# onetesla.net
KiCad netlist of a schematic drawn in EAGLE
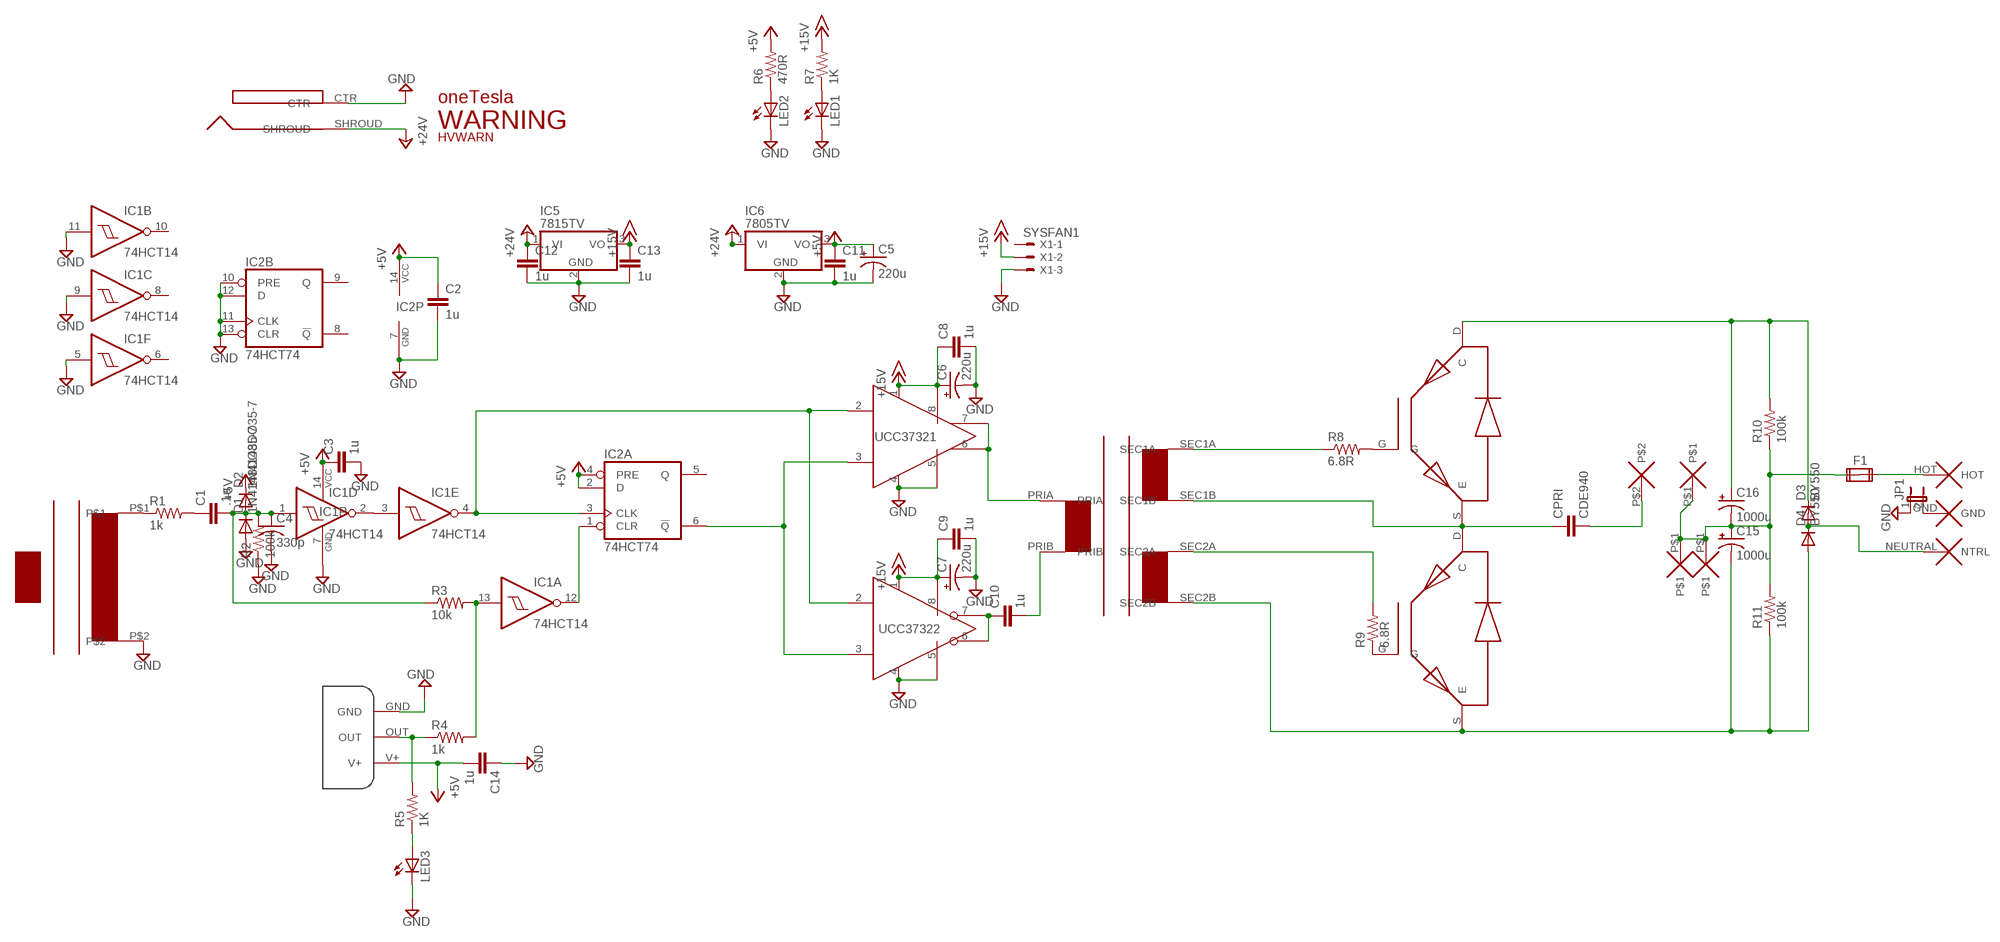
[diagram p0: schematic, sheet 1]

(export (version "E")
  (design (tool "Eeschema 10.0.6"))
  (components
    (comp (ref "C1")
      (value ".1u")
      (footprint "eagle-import:C050-024X044")
      (libsource (lib "eagle-import") (part "C-EU050-024X044"))
    )
    (comp (ref "C2")
      (value "1u")
      (footprint "eagle-import:C050-024X044")
      (libsource (lib "eagle-import") (part "C-EU050-024X044"))
    )
    (comp (ref "C3")
      (value "1u")
      (footprint "eagle-import:C050-024X044")
      (libsource (lib "eagle-import") (part "C-EU050-024X044"))
    )
    (comp (ref "C4")
      (value "330p")
      (footprint "eagle-import:C025-024X044")
      (libsource (lib "eagle-import") (part "C-US025-024X044"))
    )
    (comp (ref "C5")
      (value "220u")
      (footprint "eagle-import:E5-10,5")
      (libsource (lib "eagle-import") (part "CPOL-USE5-10.5"))
    )
    (comp (ref "C6")
      (value "220u")
      (footprint "eagle-import:E5-10,5")
      (libsource (lib "eagle-import") (part "CPOL-USE5-10.5"))
    )
    (comp (ref "C7")
      (value "220u")
      (footprint "eagle-import:E5-10,5")
      (libsource (lib "eagle-import") (part "CPOL-USE5-10.5"))
    )
    (comp (ref "C8")
      (value "1u")
      (footprint "eagle-import:C050-024X044")
      (libsource (lib "eagle-import") (part "C-EU050-024X044"))
    )
    (comp (ref "C9")
      (value "1u")
      (footprint "eagle-import:C050-024X044")
      (libsource (lib "eagle-import") (part "C-EU050-024X044"))
    )
    (comp (ref "C10")
      (value "1u")
      (footprint "eagle-import:C050-024X044")
      (libsource (lib "eagle-import") (part "C-EU050-024X044"))
    )
    (comp (ref "C11")
      (value "1u")
      (footprint "eagle-import:C050-024X044")
      (libsource (lib "eagle-import") (part "C-EU050-024X044"))
    )
    (comp (ref "C12")
      (value "1u")
      (footprint "eagle-import:C050-024X044")
      (libsource (lib "eagle-import") (part "C-EU050-024X044"))
    )
    (comp (ref "C13")
      (value "1u")
      (footprint "eagle-import:C050-024X044")
      (libsource (lib "eagle-import") (part "C-EU050-024X044"))
    )
    (comp (ref "C14")
      (value "1u")
      (footprint "eagle-import:C050-024X044")
      (libsource (lib "eagle-import") (part "C-EU050-024X044"))
    )
    (comp (ref "C15")
      (value "1000u")
      (footprint "eagle-import:EB25D")
      (libsource (lib "eagle-import") (part "CPOL-USE10-25"))
    )
    (comp (ref "C16")
      (value "1000u")
      (footprint "eagle-import:EB25D")
      (libsource (lib "eagle-import") (part "CPOL-USE10-25"))
    )
    (comp (ref "CPRI")
      (value "CDE940")
      (footprint "eagle-import:CDE940")
      (libsource (lib "eagle-import") (part "CDE940"))
    )
    (comp (ref "CT1")
      (value "TRIAD_CT")
      (footprint "eagle-import:CT2")
      (libsource (lib "eagle-import") (part "TRIAD_CT"))
    )
    (comp (ref "D1")
      (value "1N4148DO35-7")
      (footprint "eagle-import:DO35-7")
      (libsource (lib "eagle-import") (part "1N4148DO35-7"))
    )
    (comp (ref "D2")
      (value "1N4148DO35-7")
      (footprint "eagle-import:DO35-7")
      (libsource (lib "eagle-import") (part "1N4148DO35-7"))
    )
    (comp (ref "D3")
      (value "BY550")
      (footprint "eagle-import:DO27-15")
      (libsource (lib "eagle-import") (part "BY550"))
    )
    (comp (ref "D4")
      (value "BY550")
      (footprint "eagle-import:DO27-15")
      (libsource (lib "eagle-import") (part "BY550"))
    )
    (comp (ref "F1")
      (value "FUSE2P")
      (footprint "eagle-import:FUSE1")
      (libsource (lib "eagle-import") (part "FUSE2P"))
    )
    (comp (ref "FB1")
      (value "IFD95_OPTO")
      (footprint "eagle-import:IFD95")
      (libsource (lib "eagle-import") (part "IFD95_OPTO"))
    )
    (comp (ref "IC1")
      (value "74HCT14")
      (footprint "eagle-import:DIL14")
      (libsource (lib "eagle-import") (part "7414NLS"))
    )
    (comp (ref "IC2")
      (value "74HCT74")
      (footprint "eagle-import:DIL14")
      (libsource (lib "eagle-import") (part "7474NLS"))
    )
    (comp (ref "IC3")
      (value "UCC37321DIL8")
      (footprint "eagle-import:DIL08")
      (libsource (lib "eagle-import") (part "UCC37321DIL8"))
    )
    (comp (ref "IC4")
      (value "UCC37322DIL8")
      (footprint "eagle-import:DIL08")
      (libsource (lib "eagle-import") (part "UCC37322DIL8"))
    )
    (comp (ref "IC5")
      (value "7815TV")
      (footprint "eagle-import:TO220V")
      (libsource (lib "eagle-import") (part "78TV15"))
    )
    (comp (ref "IC6")
      (value "7805TV")
      (footprint "eagle-import:TO220V")
      (libsource (lib "eagle-import") (part "78TV05"))
    )
    (comp (ref "J1")
      (value "DC-IN")
      (footprint "eagle-import:DJC0202")
      (libsource (lib "eagle-import") (part "PJ-037B"))
    )
    (comp (ref "J2")
      (value "IEC")
      (footprint "eagle-import:IECPORT")
      (libsource (lib "eagle-import") (part "IEC"))
    )
    (comp (ref "JP1")
      (value "JP1E")
      (footprint "eagle-import:JP1")
      (libsource (lib "eagle-import") (part "JP1E"))
    )
    (comp (ref "LED1")
      (value "LED5MM")
      (footprint "eagle-import:LED5MM")
      (libsource (lib "eagle-import") (part "LED5MM"))
    )
    (comp (ref "LED2")
      (value "LED5MM")
      (footprint "eagle-import:LED5MM")
      (libsource (lib "eagle-import") (part "LED5MM"))
    )
    (comp (ref "LED3")
      (value "LED5MM")
      (footprint "eagle-import:LED5MM")
      (libsource (lib "eagle-import") (part "LED5MM"))
    )
    (comp (ref "LPRI")
      (value "2TERMINAL")
      (footprint "eagle-import:2TERMINAL")
      (libsource (lib "eagle-import") (part "2TERMINAL"))
    )
    (comp (ref "Q1")
      (value "FGA60N65SMD")
      (footprint "eagle-import:TO247BV")
      (libsource (lib "eagle-import") (part "FGH40N60SMD"))
    )
    (comp (ref "Q2")
      (value "FGA60N65SMD")
      (footprint "eagle-import:TO247BV")
      (libsource (lib "eagle-import") (part "FGH40N60SMD"))
    )
    (comp (ref "R1")
      (value "1k")
      (footprint "eagle-import:0922_22")
      (libsource (lib "eagle-import") (part "RES_5W"))
    )
    (comp (ref "R2")
      (value "100k")
      (footprint "eagle-import:0204_7")
      (libsource (lib "eagle-import") (part "resistor_R-US_0204/7"))
    )
    (comp (ref "R3")
      (value "10k")
      (footprint "eagle-import:0204_7")
      (libsource (lib "eagle-import") (part "resistor_R-US_0204/7"))
    )
    (comp (ref "R4")
      (value "1k")
      (footprint "eagle-import:0204_7")
      (libsource (lib "eagle-import") (part "resistor_R-US_0204/7"))
    )
    (comp (ref "R5")
      (value "1K")
      (footprint "eagle-import:0207_7")
      (libsource (lib "eagle-import") (part "R-US_0207/7"))
    )
    (comp (ref "R6")
      (value "470R")
      (footprint "eagle-import:0207_7")
      (libsource (lib "eagle-import") (part "R-US_0207/7"))
    )
    (comp (ref "R7")
      (value "1K")
      (footprint "eagle-import:0207_7")
      (libsource (lib "eagle-import") (part "R-US_0207/7"))
    )
    (comp (ref "R8")
      (value "6.8R")
      (footprint "eagle-import:0309V")
      (libsource (lib "eagle-import") (part "R-US_0309/V"))
    )
    (comp (ref "R9")
      (value "6.8R")
      (footprint "eagle-import:0309V")
      (libsource (lib "eagle-import") (part "R-US_0309/V"))
    )
    (comp (ref "R10")
      (value "100k")
      (footprint "eagle-import:0309_10")
      (libsource (lib "eagle-import") (part "resistor_R-US_0309/10"))
    )
    (comp (ref "R11")
      (value "100k")
      (footprint "eagle-import:0309_10")
      (libsource (lib "eagle-import") (part "resistor_R-US_0309/10"))
    )
    (comp (ref "U$1")
      (value "LOGO")
      (footprint "eagle-import:LOGO")
      (libsource (lib "eagle-import") (part "LOGO"))
    )
    (comp (ref "U$2")
      (value "GDT")
      (footprint "eagle-import:GDT")
      (libsource (lib "eagle-import") (part "GDT"))
    )
    (comp (ref "U$3")
      (value "WARNING")
      (footprint "eagle-import:WARNING")
      (libsource (lib "eagle-import") (part "WARNING"))
    )
    (comp (ref "U$4")
      (value "HVWARNING")
      (footprint "eagle-import:HVWARNING")
      (libsource (lib "eagle-import") (part "HVWARNING"))
    )
    (comp (ref "U$9")
      (value "12AWG_PAD")
      (footprint "eagle-import:12AWG_PAD")
      (libsource (lib "eagle-import") (part "12AWG_PAD"))
    )
    (comp (ref "U$11")
      (value "12AWG_PAD")
      (footprint "eagle-import:12AWG_PAD")
      (libsource (lib "eagle-import") (part "12AWG_PAD"))
    )
    (comp (ref "X1")
      (value "SYSFAN1")
      (footprint "eagle-import:22-23-2031")
      (fields (field (name "MF") "MOLEX") (field (name "MPN") "22-23-2031"))
      (libsource (lib "eagle-import") (part "22-23-2031"))
    )
  )
  (nets
    (net (code "1") (name "+5V") (class "Default")
      (node (ref "C11") (pin "1") (pinfunction "1_1") (pintype "passive"))
      (node (ref "C14") (pin "2") (pinfunction "2_2") (pintype "passive"))
      (node (ref "C2") (pin "1") (pinfunction "1_1") (pintype "passive"))
      (node (ref "C3") (pin "1") (pinfunction "1_1") (pintype "passive"))
      (node (ref "C5") (pin "+") (pinfunction "+_+") (pintype "passive"))
      (node (ref "D2") (pin "C") (pinfunction "C_C") (pintype "passive"))
      (node (ref "FB1") (pin "V+") (pinfunction "V+_V+") (pintype "bidirectional"))
      (node (ref "IC1") (pin "14") (pinfunction "VCC_14") (pintype "power_in"))
      (node (ref "IC2") (pin "14") (pinfunction "VCC_14") (pintype "power_in"))
      (node (ref "IC2") (pin "2") (pinfunction "D_2") (pintype "input"))
      (node (ref "IC2") (pin "4") (pinfunction "PRE_4") (pintype "input"))
      (node (ref "IC6") (pin "3") (pinfunction "VO_3") (pintype "passive"))
      (node (ref "R6") (pin "2") (pinfunction "2_2") (pintype "passive"))
    )
    (net (code "2") (name "+15V") (class "Default")
      (node (ref "C13") (pin "1") (pinfunction "1_1") (pintype "passive"))
      (node (ref "C6") (pin "+") (pinfunction "+_+") (pintype "passive"))
      (node (ref "C7") (pin "+") (pinfunction "+_+") (pintype "passive"))
      (node (ref "C8") (pin "1") (pinfunction "1_1") (pintype "passive"))
      (node (ref "C9") (pin "1") (pinfunction "1_1") (pintype "passive"))
      (node (ref "IC3") (pin "1") (pinfunction "1_VDD_1") (pintype "power_in"))
      (node (ref "IC3") (pin "8") (pinfunction "8_VDD_8") (pintype "power_in"))
      (node (ref "IC4") (pin "1") (pinfunction "1_VDD_1") (pintype "power_in"))
      (node (ref "IC4") (pin "8") (pinfunction "8_VDD_8") (pintype "power_in"))
      (node (ref "IC5") (pin "3") (pinfunction "VO_3") (pintype "passive"))
      (node (ref "R7") (pin "2") (pinfunction "2_2") (pintype "passive"))
      (node (ref "X1") (pin "2") (pinfunction "S_2") (pintype "passive"))
    )
    (net (code "3") (name "+24V") (class "Default")
      (node (ref "C12") (pin "1") (pinfunction "1_1") (pintype "passive"))
      (node (ref "IC5") (pin "1") (pinfunction "VI_1") (pintype "input"))
      (node (ref "IC6") (pin "1") (pinfunction "VI_1") (pintype "input"))
      (node (ref "J1") (pin "SHROUD") (pinfunction "SHROUD_SHROUD") (pintype "bidirectional"))
    )
    (net (code "4") (name "GND") (class "Default")
      (node (ref "C11") (pin "2") (pinfunction "2_2") (pintype "passive"))
      (node (ref "C12") (pin "2") (pinfunction "2_2") (pintype "passive"))
      (node (ref "C13") (pin "2") (pinfunction "2_2") (pintype "passive"))
      (node (ref "C14") (pin "1") (pinfunction "1_1") (pintype "passive"))
      (node (ref "C2") (pin "2") (pinfunction "2_2") (pintype "passive"))
      (node (ref "C3") (pin "2") (pinfunction "2_2") (pintype "passive"))
      (node (ref "C4") (pin "2") (pinfunction "2_2") (pintype "passive"))
      (node (ref "C5") (pin "-") (pinfunction "-_-") (pintype "passive"))
      (node (ref "C6") (pin "-") (pinfunction "-_-") (pintype "passive"))
      (node (ref "C7") (pin "-") (pinfunction "-_-") (pintype "passive"))
      (node (ref "C8") (pin "2") (pinfunction "2_2") (pintype "passive"))
      (node (ref "C9") (pin "2") (pinfunction "2_2") (pintype "passive"))
      (node (ref "CT1") (pin "P$2") (pinfunction "P$2_P$2") (pintype "output"))
      (node (ref "D1") (pin "A") (pinfunction "A_A") (pintype "passive"))
      (node (ref "FB1") (pin "GND") (pinfunction "GND_GND") (pintype "bidirectional"))
      (node (ref "IC1") (pin "11") (pinfunction "I_11") (pintype "input"))
      (node (ref "IC1") (pin "5") (pinfunction "I_5") (pintype "input"))
      (node (ref "IC1") (pin "7") (pinfunction "GND_7") (pintype "power_in"))
      (node (ref "IC1") (pin "9") (pinfunction "I_9") (pintype "input"))
      (node (ref "IC2") (pin "10") (pinfunction "PRE_10") (pintype "input"))
      (node (ref "IC2") (pin "11") (pinfunction "CLK_11") (pintype "input"))
      (node (ref "IC2") (pin "12") (pinfunction "D_12") (pintype "input"))
      (node (ref "IC2") (pin "13") (pinfunction "CLR_13") (pintype "input"))
      (node (ref "IC2") (pin "7") (pinfunction "GND_7") (pintype "power_in"))
      (node (ref "IC3") (pin "4") (pinfunction "4_AGND_4") (pintype "power_in"))
      (node (ref "IC3") (pin "5") (pinfunction "5_PGND_5") (pintype "power_in"))
      (node (ref "IC4") (pin "4") (pinfunction "4_AGND_4") (pintype "power_in"))
      (node (ref "IC4") (pin "5") (pinfunction "5_PGND_5") (pintype "power_in"))
      (node (ref "IC5") (pin "2") (pinfunction "GND_2") (pintype "passive"))
      (node (ref "IC6") (pin "2") (pinfunction "GND_2") (pintype "passive"))
      (node (ref "J1") (pin "CTR") (pinfunction "CTR_CTR") (pintype "bidirectional"))
      (node (ref "JP1") (pin "1") (pinfunction "1_1") (pintype "passive"))
      (node (ref "LED1") (pin "K") (pinfunction "C_K") (pintype "passive"))
      (node (ref "LED2") (pin "K") (pinfunction "C_K") (pintype "passive"))
      (node (ref "LED3") (pin "K") (pinfunction "C_K") (pintype "passive"))
      (node (ref "R2") (pin "1") (pinfunction "1_1") (pintype "passive"))
      (node (ref "X1") (pin "3") (pinfunction "S_3") (pintype "passive"))
    )
    (net (code "5") (name "Net-(C1-Pad1)") (class "Default")
      (node (ref "C1") (pin "1") (pinfunction "1_1") (pintype "passive"))
      (node (ref "R1") (pin "2") (pinfunction "2_2") (pintype "passive"))
    )
    (net (code "6") (name "Net-(C10-Pad2)") (class "Default")
      (node (ref "C10") (pin "2") (pinfunction "2_2") (pintype "passive"))
      (node (ref "U$2") (pin "PRIB") (pinfunction "PRIB_PRIB") (pintype "input"))
    )
    (net (code "7") (name "Net-(C15-Pad+)") (class "Default")
      (node (ref "C15") (pin "+") (pinfunction "+_+") (pintype "passive"))
      (node (ref "C16") (pin "-") (pinfunction "-_-") (pintype "passive"))
      (node (ref "F1") (pin "1A") (pinfunction "1A_1A") (pintype "passive"))
      (node (ref "F1") (pin "1B") (pinfunction "1B_1B") (pintype "passive"))
      (node (ref "LPRI") (pin "P$1") (pinfunction "P$1_P$1") (pintype "bidirectional"))
      (node (ref "R10") (pin "1") (pinfunction "1_1") (pintype "passive"))
      (node (ref "R11") (pin "2") (pinfunction "2_2") (pintype "passive"))
      (node (ref "U$11") (pin "P$1") (pinfunction "P$1_P$1") (pintype "bidirectional"))
      (node (ref "U$9") (pin "P$1") (pinfunction "P$1_P$1") (pintype "bidirectional"))
    )
    (net (code "8") (name "Net-(CPRI-1)") (class "Default")
      (node (ref "CPRI") (pin "P$1") (pinfunction "1_P$1") (pintype "passive"))
      (node (ref "Q1") (pin "S") (pinfunction "E_S") (pintype "bidirectional"))
      (node (ref "Q2") (pin "D") (pinfunction "C_D") (pintype "bidirectional"))
      (node (ref "U$2") (pin "SEC1B") (pinfunction "SEC1B_SEC1B") (pintype "output"))
    )
    (net (code "9") (name "Net-(CPRI-2)") (class "Default")
      (node (ref "CPRI") (pin "P$2") (pinfunction "2_P$2") (pintype "passive"))
      (node (ref "LPRI") (pin "P$2") (pinfunction "P$2_P$2") (pintype "bidirectional"))
    )
    (net (code "10") (name "Net-(CT1-PadP$1)") (class "Default")
      (node (ref "CT1") (pin "P$1") (pinfunction "P$1_P$1") (pintype "output"))
      (node (ref "R1") (pin "1") (pinfunction "1_1") (pintype "passive"))
    )
    (net (code "11") (name "Net-(F1-Pad2A)") (class "Default")
      (node (ref "F1") (pin "2A") (pinfunction "2A_2A") (pintype "passive"))
      (node (ref "J2") (pin "HOT") (pinfunction "HOT_HOT") (pintype "bidirectional"))
    )
    (net (code "12") (name "Net-(FB1-PadOUT)") (class "Default")
      (node (ref "FB1") (pin "OUT") (pinfunction "OUT_OUT") (pintype "bidirectional"))
      (node (ref "R4") (pin "1") (pinfunction "1_1") (pintype "passive"))
      (node (ref "R5") (pin "2") (pinfunction "2_2") (pintype "passive"))
    )
    (net (code "13") (name "Net-(IC1A-I)") (class "Default")
      (node (ref "IC1") (pin "13") (pinfunction "I_13") (pintype "input"))
      (node (ref "R3") (pin "2") (pinfunction "2_2") (pintype "passive"))
      (node (ref "R4") (pin "2") (pinfunction "2_2") (pintype "passive"))
    )
    (net (code "14") (name "Net-(IC1A-O)") (class "Default")
      (node (ref "IC1") (pin "12") (pinfunction "O_12") (pintype "output"))
      (node (ref "IC2") (pin "1") (pinfunction "CLR_1") (pintype "input"))
    )
    (net (code "15") (name "Net-(IC1D-I)") (class "Default")
      (node (ref "C1") (pin "2") (pinfunction "2_2") (pintype "passive"))
      (node (ref "C4") (pin "1") (pinfunction "1_1") (pintype "passive"))
      (node (ref "D1") (pin "C") (pinfunction "C_C") (pintype "passive"))
      (node (ref "D2") (pin "A") (pinfunction "A_A") (pintype "passive"))
      (node (ref "IC1") (pin "1") (pinfunction "I_1") (pintype "input"))
      (node (ref "R2") (pin "2") (pinfunction "2_2") (pintype "passive"))
      (node (ref "R3") (pin "1") (pinfunction "1_1") (pintype "passive"))
    )
    (net (code "16") (name "Net-(IC1D-O)") (class "Default")
      (node (ref "IC1") (pin "2") (pinfunction "O_2") (pintype "output"))
      (node (ref "IC1") (pin "3") (pinfunction "I_3") (pintype "input"))
    )
    (net (code "17") (name "Net-(IC1E-O)") (class "Default")
      (node (ref "IC1") (pin "4") (pinfunction "O_4") (pintype "output"))
      (node (ref "IC2") (pin "3") (pinfunction "CLK_3") (pintype "input"))
      (node (ref "IC3") (pin "2") (pinfunction "2_IN_2") (pintype "input"))
      (node (ref "IC4") (pin "2") (pinfunction "2_IN_2") (pintype "input"))
    )
    (net (code "18") (name "Net-(IC2A-~{Q})") (class "Default")
      (node (ref "IC2") (pin "6") (pinfunction "~{Q}_6") (pintype "output"))
      (node (ref "IC3") (pin "3") (pinfunction "3_ENBL_3") (pintype "input"))
      (node (ref "IC4") (pin "3") (pinfunction "3_ENBL_3") (pintype "input"))
    )
    (net (code "19") (name "Net-(IC3-6_OUT)") (class "Default")
      (node (ref "IC3") (pin "6") (pinfunction "6_OUT_6") (pintype "output"))
      (node (ref "IC3") (pin "7") (pinfunction "7_OUT_7") (pintype "output"))
      (node (ref "U$2") (pin "PRIA") (pinfunction "PRIA_PRIA") (pintype "input"))
    )
    (net (code "20") (name "Net-(IC4-6_OUT)") (class "Default")
      (node (ref "C10") (pin "1") (pinfunction "1_1") (pintype "passive"))
      (node (ref "IC4") (pin "6") (pinfunction "6_OUT_6") (pintype "output"))
      (node (ref "IC4") (pin "7") (pinfunction "7_OUT_7") (pintype "output"))
    )
    (net (code "21") (name "Net-(J2-NTRL)") (class "Default")
      (node (ref "D3") (pin "A") (pinfunction "A_A") (pintype "passive"))
      (node (ref "D4") (pin "C") (pinfunction "C_C") (pintype "passive"))
      (node (ref "J2") (pin "NEUTRAL") (pinfunction "NTRL_NEUTRAL") (pintype "bidirectional"))
    )
    (net (code "22") (name "Net-(J2-PadGND)") (class "Default")
      (node (ref "J2") (pin "GND") (pinfunction "GND_GND") (pintype "bidirectional"))
      (node (ref "JP1") (pin "2") (pinfunction "2_2") (pintype "passive"))
    )
    (net (code "23") (name "Net-(LED1-PadA)") (class "Default")
      (node (ref "LED1") (pin "A") (pinfunction "A_A") (pintype "passive"))
      (node (ref "R7") (pin "1") (pinfunction "1_1") (pintype "passive"))
    )
    (net (code "24") (name "Net-(LED2-PadA)") (class "Default")
      (node (ref "LED2") (pin "A") (pinfunction "A_A") (pintype "passive"))
      (node (ref "R6") (pin "1") (pinfunction "1_1") (pintype "passive"))
    )
    (net (code "25") (name "Net-(LED3-PadA)") (class "Default")
      (node (ref "LED3") (pin "A") (pinfunction "A_A") (pintype "passive"))
      (node (ref "R5") (pin "1") (pinfunction "1_1") (pintype "passive"))
    )
    (net (code "26") (name "Net-(Q1-C)") (class "Default")
      (node (ref "C16") (pin "+") (pinfunction "+_+") (pintype "passive"))
      (node (ref "D3") (pin "C") (pinfunction "C_C") (pintype "passive"))
      (node (ref "Q1") (pin "D") (pinfunction "C_D") (pintype "bidirectional"))
      (node (ref "R10") (pin "2") (pinfunction "2_2") (pintype "passive"))
    )
    (net (code "27") (name "Net-(Q1-PadG)") (class "Default")
      (node (ref "Q1") (pin "G") (pinfunction "G_G") (pintype "bidirectional"))
      (node (ref "R8") (pin "2") (pinfunction "2_2") (pintype "passive"))
    )
    (net (code "28") (name "Net-(Q2-E)") (class "Default")
      (node (ref "C15") (pin "-") (pinfunction "-_-") (pintype "passive"))
      (node (ref "D4") (pin "A") (pinfunction "A_A") (pintype "passive"))
      (node (ref "Q2") (pin "S") (pinfunction "E_S") (pintype "bidirectional"))
      (node (ref "R11") (pin "1") (pinfunction "1_1") (pintype "passive"))
      (node (ref "U$2") (pin "SEC2B") (pinfunction "SEC2B_SEC2B") (pintype "output"))
    )
    (net (code "29") (name "Net-(Q2-PadG)") (class "Default")
      (node (ref "Q2") (pin "G") (pinfunction "G_G") (pintype "bidirectional"))
      (node (ref "R9") (pin "1") (pinfunction "1_1") (pintype "passive"))
    )
    (net (code "30") (name "Net-(R8-Pad1)") (class "Default")
      (node (ref "R8") (pin "1") (pinfunction "1_1") (pintype "passive"))
      (node (ref "U$2") (pin "SEC1A") (pinfunction "SEC1A_SEC1A") (pintype "output"))
    )
    (net (code "31") (name "Net-(R9-Pad2)") (class "Default")
      (node (ref "R9") (pin "2") (pinfunction "2_2") (pintype "passive"))
      (node (ref "U$2") (pin "SEC2A") (pinfunction "SEC2A_SEC2A") (pintype "output"))
    )
    (net (code "32") (name "unconnected-(F1-Pad2B)") (class "Default")
      (node (ref "F1") (pin "2B") (pinfunction "2B_2B") (pintype "passive"))
    )
    (net (code "33") (name "unconnected-(IC1B-O-Pad10)") (class "Default")
      (node (ref "IC1") (pin "10") (pinfunction "O_10") (pintype "output"))
    )
    (net (code "34") (name "unconnected-(IC1C-O-Pad8)") (class "Default")
      (node (ref "IC1") (pin "8") (pinfunction "O_8") (pintype "output"))
    )
    (net (code "35") (name "unconnected-(IC1F-O-Pad6)") (class "Default")
      (node (ref "IC1") (pin "6") (pinfunction "O_6") (pintype "output"))
    )
    (net (code "36") (name "unconnected-(IC2A-Q-Pad5)") (class "Default")
      (node (ref "IC2") (pin "5") (pinfunction "Q_5") (pintype "output"))
    )
    (net (code "37") (name "unconnected-(IC2B-Q-Pad9)") (class "Default")
      (node (ref "IC2") (pin "9") (pinfunction "Q_9") (pintype "output"))
    )
    (net (code "38") (name "unconnected-(IC2B-~{Q}-Pad8)") (class "Default")
      (node (ref "IC2") (pin "8") (pinfunction "~{Q}_8") (pintype "output"))
    )
    (net (code "39") (name "unconnected-(X1A-S-Pad1)") (class "Default")
      (node (ref "X1") (pin "1") (pinfunction "S_1") (pintype "passive"))
    )
  )
)
